# design.net
KiCad netlist of a schematic drawn in Altium Designer
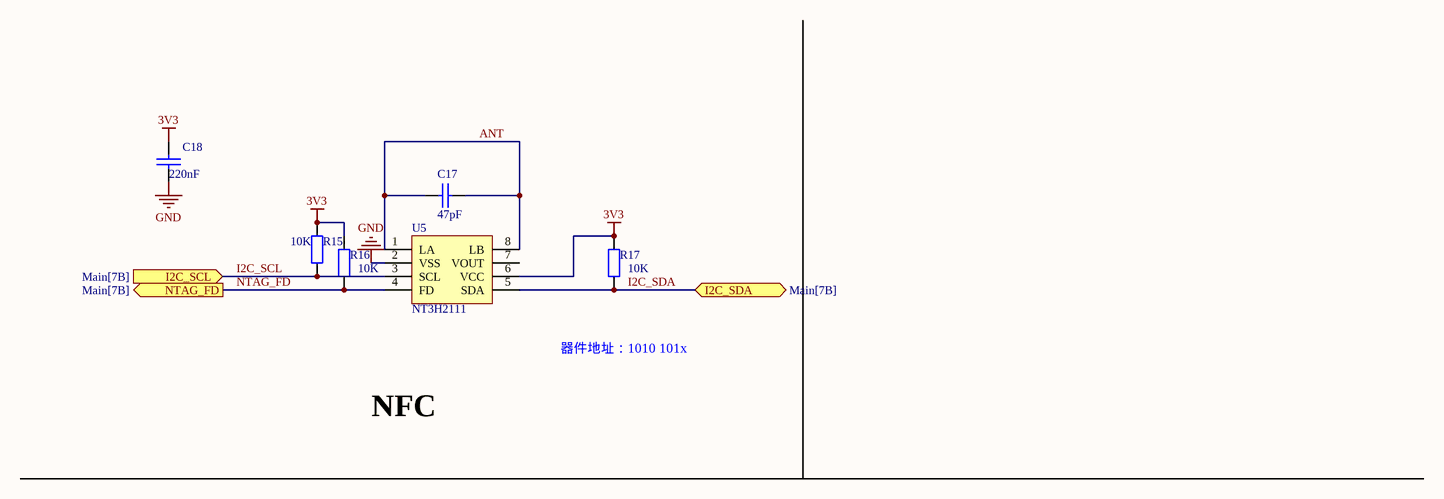
[diagram p0: 外围.SchDoc]

(export (version "E")
  (design (tool "Eeschema 10.0.6"))
  (components
    (comp (ref "C17")
      (value "47pF")
      (footprint "0402_C")
      (description "Capacitor")
      (libsource (lib "RFID") (part "CAP"))
    )
    (comp (ref "C18")
      (value "220nF")
      (footprint "0201_C")
      (description "Capacitor")
      (libsource (lib "RFID") (part "CAP"))
    )
    (comp (ref "R15")
      (value "10K")
      (footprint "0201_R")
      (description "Resistor")
      (fields (field (name "Comment") "Res"))
      (libsource (lib "RFID") (part "Res2"))
    )
    (comp (ref "R16")
      (value "10K")
      (footprint "0201_R")
      (description "Resistor")
      (fields (field (name "Comment") "Res"))
      (libsource (lib "RFID") (part "Res2"))
    )
    (comp (ref "R17")
      (value "10K")
      (footprint "0201_R")
      (description "Resistor")
      (fields (field (name "Comment") "Res"))
      (libsource (lib "RFID") (part "Res2"))
    )
    (comp (ref "U5") (value "NT3H2111") (footprint "TSSOP-8") (libsource (lib "RFID") (part "NT3H1101")))
  )
  (nets
    (net (code "1") (name "/ANT") (class "Default")
      (node (ref "C17") (pin "1") (pinfunction "1_1") (pintype "passive"))
      (node (ref "C17") (pin "2") (pinfunction "2_2") (pintype "passive"))
      (node (ref "U5") (pin "1") (pinfunction "LA_1") (pintype "power_in"))
      (node (ref "U5") (pin "8") (pinfunction "LB_8") (pintype "power_in"))
    )
    (net (code "2") (name "/I2C_SCL") (class "Default")
      (node (ref "R15") (pin "2") (pinfunction "2_2") (pintype "passive"))
      (node (ref "U5") (pin "3") (pinfunction "SCL_3") (pintype "power_in"))
    )
    (net (code "3") (name "/I2C_SDA") (class "Default")
      (node (ref "R17") (pin "2") (pinfunction "2_2") (pintype "passive"))
      (node (ref "U5") (pin "5") (pinfunction "SDA_5") (pintype "power_in"))
    )
    (net (code "4") (name "/NTAG_FD") (class "Default")
      (node (ref "R16") (pin "2") (pinfunction "2_2") (pintype "passive"))
      (node (ref "U5") (pin "4") (pinfunction "FD_4") (pintype "power_in"))
    )
    (net (code "5") (name "3V3") (class "Default")
      (node (ref "C18") (pin "1") (pinfunction "1_1") (pintype "passive"))
      (node (ref "R15") (pin "1") (pinfunction "1_1") (pintype "passive"))
      (node (ref "R16") (pin "1") (pinfunction "1_1") (pintype "passive"))
      (node (ref "R17") (pin "1") (pinfunction "1_1") (pintype "passive"))
      (node (ref "U5") (pin "6") (pinfunction "VCC_6") (pintype "power_in"))
    )
    (net (code "6") (name "GND") (class "Default")
      (node (ref "C18") (pin "2") (pinfunction "2_2") (pintype "passive"))
      (node (ref "U5") (pin "2") (pinfunction "VSS_2") (pintype "power_in"))
    )
    (net (code "7") (name "unconnected-(U5-VOUT-Pad7)") (class "Default")
      (node (ref "U5") (pin "7") (pinfunction "VOUT_7") (pintype "power_in"))
    )
  )
)
